# 3DM_V2.net
KiCad netlist of a schematic drawn in EAGLE
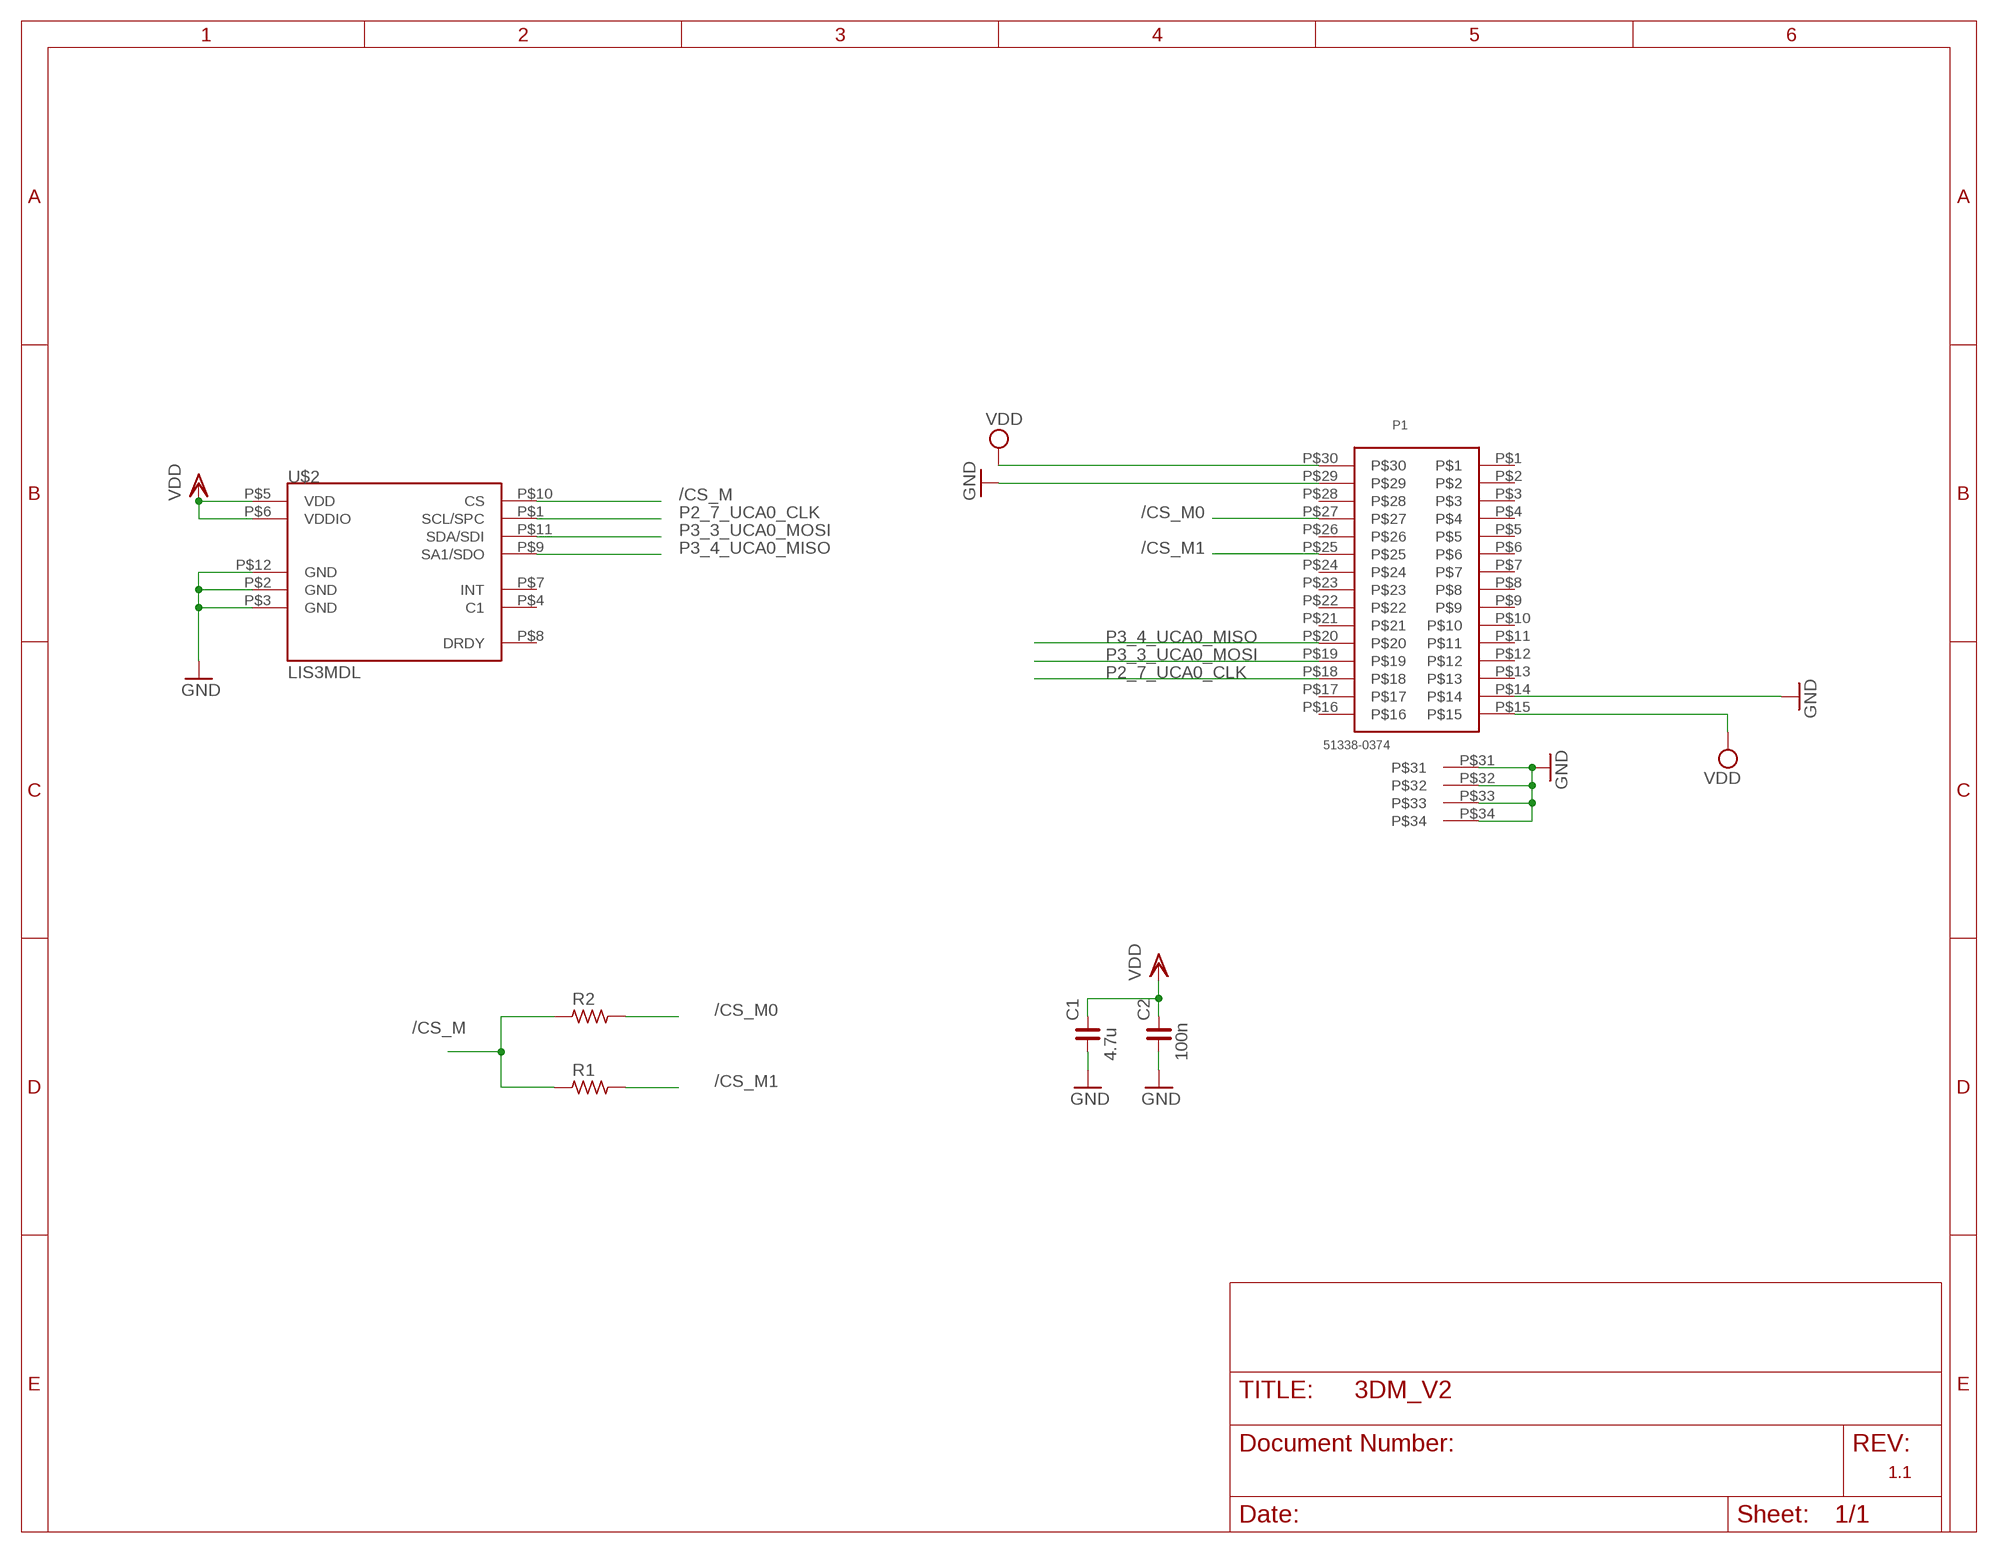
[diagram p0: schematic, sheet 1]

(export (version "E")
  (design (tool "Eeschema 10.0.6"))
  (components
    (comp (ref "C1")
      (value "4.7u")
      (footprint "eagle-import:C0402")
      (libsource (lib "eagle-import") (part "C_0402"))
    )
    (comp (ref "C2")
      (value "100n")
      (footprint "eagle-import:C0402")
      (libsource (lib "eagle-import") (part "C_0402"))
    )
    (comp (ref "P1")
      (value "51338-0374")
      (footprint "eagle-import:51338-0374_RECEPTACLE")
      (libsource (lib "eagle-import") (part "51338-0374_RECEPTACLE"))
    )
    (comp (ref "R1")
      (value "R_0402")
      (footprint "eagle-import:R0402")
      (libsource (lib "eagle-import") (part "R_0402"))
    )
    (comp (ref "R2")
      (value "R_0402")
      (footprint "eagle-import:R0402")
      (libsource (lib "eagle-import") (part "R_0402"))
    )
    (comp (ref "U$2")
      (value "LIS3MDL")
      (footprint "eagle-import:VFLGA-2X2X1")
      (libsource (lib "eagle-import") (part "LIS3MDL"))
    )
  )
  (nets
    (net (code "1") (name "/P2_7_UCA0_CLK") (class "Default")
      (node (ref "P1") (pin "P$18") (pinfunction "P$18_P$18") (pintype "bidirectional"))
      (node (ref "U$2") (pin "P$1") (pinfunction "SCL/SPC_P$1") (pintype "bidirectional"))
    )
    (net (code "2") (name "/P3_3_UCA0_MOSI") (class "Default")
      (node (ref "P1") (pin "P$19") (pinfunction "P$19_P$19") (pintype "bidirectional"))
      (node (ref "U$2") (pin "P$11") (pinfunction "SDA/SDI_P$11") (pintype "bidirectional"))
    )
    (net (code "3") (name "/P3_4_UCA0_MISO") (class "Default")
      (node (ref "P1") (pin "P$20") (pinfunction "P$20_P$20") (pintype "bidirectional"))
      (node (ref "U$2") (pin "P$9") (pinfunction "SA1/SDO_P$9") (pintype "bidirectional"))
    )
    (net (code "4") (name "/{slash}CS_M") (class "Default")
      (node (ref "R1") (pin "1") (pinfunction "1_1") (pintype "passive"))
      (node (ref "R2") (pin "1") (pinfunction "1_1") (pintype "passive"))
      (node (ref "U$2") (pin "P$10") (pinfunction "CS_P$10") (pintype "bidirectional"))
    )
    (net (code "5") (name "/{slash}CS_M0") (class "Default")
      (node (ref "P1") (pin "P$27") (pinfunction "P$27_P$27") (pintype "bidirectional"))
      (node (ref "R2") (pin "2") (pinfunction "2_2") (pintype "passive"))
    )
    (net (code "6") (name "/{slash}CS_M1") (class "Default")
      (node (ref "P1") (pin "P$25") (pinfunction "P$25_P$25") (pintype "bidirectional"))
      (node (ref "R1") (pin "2") (pinfunction "2_2") (pintype "passive"))
    )
    (net (code "7") (name "GND") (class "Default")
      (node (ref "C1") (pin "1") (pinfunction "1_1") (pintype "passive"))
      (node (ref "C2") (pin "1") (pinfunction "1_1") (pintype "passive"))
      (node (ref "P1") (pin "P$14") (pinfunction "P$14_P$14") (pintype "bidirectional"))
      (node (ref "P1") (pin "P$29") (pinfunction "P$29_P$29") (pintype "bidirectional"))
      (node (ref "P1") (pin "P$31") (pinfunction "P$31_P$31") (pintype "bidirectional"))
      (node (ref "P1") (pin "P$32") (pinfunction "P$32_P$32") (pintype "bidirectional"))
      (node (ref "P1") (pin "P$33") (pinfunction "P$33_P$33") (pintype "bidirectional"))
      (node (ref "P1") (pin "P$34") (pinfunction "P$34_P$34") (pintype "bidirectional"))
      (node (ref "U$2") (pin "P$12") (pinfunction "GND_P$12") (pintype "bidirectional"))
      (node (ref "U$2") (pin "P$2") (pinfunction "GND_P$2") (pintype "bidirectional"))
      (node (ref "U$2") (pin "P$3") (pinfunction "GND_P$3") (pintype "bidirectional"))
    )
    (net (code "8") (name "VDD") (class "Default")
      (node (ref "C1") (pin "2") (pinfunction "2_2") (pintype "passive"))
      (node (ref "C2") (pin "2") (pinfunction "2_2") (pintype "passive"))
      (node (ref "P1") (pin "P$15") (pinfunction "P$15_P$15") (pintype "bidirectional"))
      (node (ref "P1") (pin "P$30") (pinfunction "P$30_P$30") (pintype "bidirectional"))
      (node (ref "U$2") (pin "P$5") (pinfunction "VDD_P$5") (pintype "bidirectional"))
      (node (ref "U$2") (pin "P$6") (pinfunction "VDDIO_P$6") (pintype "bidirectional"))
    )
    (net (code "9") (name "unconnected-(P1-PadP$1)") (class "Default")
      (node (ref "P1") (pin "P$1") (pinfunction "P$1_P$1") (pintype "bidirectional"))
    )
    (net (code "10") (name "unconnected-(P1-PadP$2)") (class "Default")
      (node (ref "P1") (pin "P$2") (pinfunction "P$2_P$2") (pintype "bidirectional"))
    )
    (net (code "11") (name "unconnected-(P1-PadP$3)") (class "Default")
      (node (ref "P1") (pin "P$3") (pinfunction "P$3_P$3") (pintype "bidirectional"))
    )
    (net (code "12") (name "unconnected-(P1-PadP$4)") (class "Default")
      (node (ref "P1") (pin "P$4") (pinfunction "P$4_P$4") (pintype "bidirectional"))
    )
    (net (code "13") (name "unconnected-(P1-PadP$5)") (class "Default")
      (node (ref "P1") (pin "P$5") (pinfunction "P$5_P$5") (pintype "bidirectional"))
    )
    (net (code "14") (name "unconnected-(P1-PadP$6)") (class "Default")
      (node (ref "P1") (pin "P$6") (pinfunction "P$6_P$6") (pintype "bidirectional"))
    )
    (net (code "15") (name "unconnected-(P1-PadP$7)") (class "Default")
      (node (ref "P1") (pin "P$7") (pinfunction "P$7_P$7") (pintype "bidirectional"))
    )
    (net (code "16") (name "unconnected-(P1-PadP$8)") (class "Default")
      (node (ref "P1") (pin "P$8") (pinfunction "P$8_P$8") (pintype "bidirectional"))
    )
    (net (code "17") (name "unconnected-(P1-PadP$9)") (class "Default")
      (node (ref "P1") (pin "P$9") (pinfunction "P$9_P$9") (pintype "bidirectional"))
    )
    (net (code "18") (name "unconnected-(P1-PadP$10)") (class "Default")
      (node (ref "P1") (pin "P$10") (pinfunction "P$10_P$10") (pintype "bidirectional"))
    )
    (net (code "19") (name "unconnected-(P1-PadP$11)") (class "Default")
      (node (ref "P1") (pin "P$11") (pinfunction "P$11_P$11") (pintype "bidirectional"))
    )
    (net (code "20") (name "unconnected-(P1-PadP$12)") (class "Default")
      (node (ref "P1") (pin "P$12") (pinfunction "P$12_P$12") (pintype "bidirectional"))
    )
    (net (code "21") (name "unconnected-(P1-PadP$13)") (class "Default")
      (node (ref "P1") (pin "P$13") (pinfunction "P$13_P$13") (pintype "bidirectional"))
    )
    (net (code "22") (name "unconnected-(P1-PadP$16)") (class "Default")
      (node (ref "P1") (pin "P$16") (pinfunction "P$16_P$16") (pintype "bidirectional"))
    )
    (net (code "23") (name "unconnected-(P1-PadP$17)") (class "Default")
      (node (ref "P1") (pin "P$17") (pinfunction "P$17_P$17") (pintype "bidirectional"))
    )
    (net (code "24") (name "unconnected-(P1-PadP$21)") (class "Default")
      (node (ref "P1") (pin "P$21") (pinfunction "P$21_P$21") (pintype "bidirectional"))
    )
    (net (code "25") (name "unconnected-(P1-PadP$22)") (class "Default")
      (node (ref "P1") (pin "P$22") (pinfunction "P$22_P$22") (pintype "bidirectional"))
    )
    (net (code "26") (name "unconnected-(P1-PadP$23)") (class "Default")
      (node (ref "P1") (pin "P$23") (pinfunction "P$23_P$23") (pintype "bidirectional"))
    )
    (net (code "27") (name "unconnected-(P1-PadP$24)") (class "Default")
      (node (ref "P1") (pin "P$24") (pinfunction "P$24_P$24") (pintype "bidirectional"))
    )
    (net (code "28") (name "unconnected-(P1-PadP$26)") (class "Default")
      (node (ref "P1") (pin "P$26") (pinfunction "P$26_P$26") (pintype "bidirectional"))
    )
    (net (code "29") (name "unconnected-(P1-PadP$28)") (class "Default")
      (node (ref "P1") (pin "P$28") (pinfunction "P$28_P$28") (pintype "bidirectional"))
    )
    (net (code "30") (name "unconnected-(U$2-C1-PadP$4)") (class "Default")
      (node (ref "U$2") (pin "P$4") (pinfunction "C1_P$4") (pintype "bidirectional"))
    )
    (net (code "31") (name "unconnected-(U$2-DRDY-PadP$8)") (class "Default")
      (node (ref "U$2") (pin "P$8") (pinfunction "DRDY_P$8") (pintype "bidirectional"))
    )
    (net (code "32") (name "unconnected-(U$2-INT-PadP$7)") (class "Default")
      (node (ref "U$2") (pin "P$7") (pinfunction "INT_P$7") (pintype "bidirectional"))
    )
  )
)
